# UV_board.net
KiCad netlist of a schematic drawn in Altium Designer
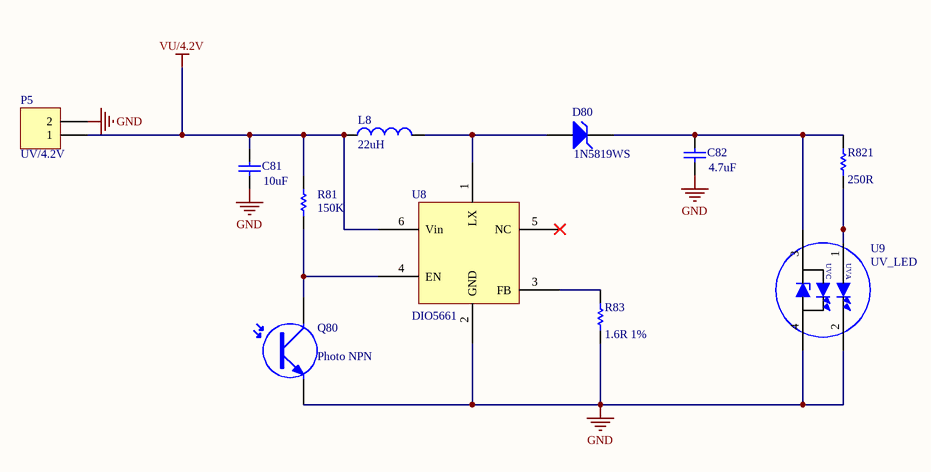
[diagram p0: UV_board.SchDoc]

(export (version "E")
  (design (tool "Eeschema 10.0.6"))
  (components
    (comp (ref "C81")
      (value "10uF")
      (footprint "C0805")
      (description "电容")
      (fields (field (name "Comment") "Cap") (field (name "PUBLISHER") "Altium Limited"))
      (libsource (lib "Miscellaneous Devices") (part "Cap"))
    )
    (comp (ref "C82")
      (value "4.7uF")
      (footprint "C0402")
      (description "电容")
      (fields (field (name "Comment") "Cap") (field (name "PUBLISHER") "Altium Limited"))
      (libsource (lib "Miscellaneous Devices") (part "Cap"))
    )
    (comp (ref "D80")
      (value "1N5819WS")
      (footprint "SOD-323")
      (description "二极管")
      (fields (field (name "PUBLISHER") "Altium Limited"))
      (libsource (lib "Miscellaneous Devices") (part "D Zener"))
    )
    (comp (ref "L8")
      (value "22uH")
      (footprint "CD32")
      (description "功率电感")
      (fields (field (name "Comment") "Inductor") (field (name "PUBLISHER") "Altium Limited"))
      (libsource (lib "Miscellaneous Devices") (part "Inductor"))
    )
    (comp (ref "P5")
      (value "UV/4.2V")
      (footprint "CON_1.25MM_2P")
      (description "UV灯电源接口")
      (fields (field (name "PUBLISHER") "Altium Limited"))
      (libsource (lib "Miscellaneous Connectors") (part "Header 2"))
    )
    (comp (ref "Q80")
      (value "Photo NPN")
      (footprint "PT0603")
      (description "光敏三极管")
      (fields (field (name "PUBLISHER") "Altium Limited"))
      (libsource (lib "Miscellaneous Devices") (part "Photo NPN"))
    )
    (comp (ref "R81")
      (value "150K")
      (footprint "R0402")
      (description "电阻")
      (fields (field (name "Comment") "Res1") (field (name "PUBLISHER") "Altium Limited"))
      (libsource (lib "Miscellaneous Devices") (part "Res1"))
    )
    (comp (ref "R83")
      (value "1.6R 1%")
      (footprint "R0402")
      (description "电阻")
      (fields (field (name "Comment") "Res1") (field (name "PUBLISHER") "Altium Limited"))
      (libsource (lib "Miscellaneous Devices") (part "Res1"))
    )
    (comp (ref "R821")
      (value "250R")
      (footprint "R0402")
      (description "电阻")
      (fields (field (name "Comment") "Res1") (field (name "PUBLISHER") "Altium Limited"))
      (libsource (lib "Miscellaneous Devices") (part "Res1"))
    )
    (comp (ref "U8")
      (value "DIO5661")
      (footprint "SOT23-6-1")
      (description "恒流IC")
      (libsource (lib "shajunbei") (part "DIO5661"))
    )
    (comp (ref "U9") (value "UV_LED") (footprint "SH35AH") (libsource (lib "shajunbei") (part "UV_LED")))
  )
  (nets
    (net (code "1") (name "GND") (class "Default")
      (node (ref "C81") (pin "2") (pinfunction "2_2") (pintype "passive"))
      (node (ref "C82") (pin "2") (pinfunction "2_2") (pintype "passive"))
      (node (ref "P5") (pin "2") (pinfunction "2_2") (pintype "passive"))
      (node (ref "Q80") (pin "3") (pinfunction "E_3") (pintype "passive"))
      (node (ref "R83") (pin "1") (pinfunction "1_1") (pintype "passive"))
      (node (ref "U8") (pin "2") (pinfunction "GND_2") (pintype "passive"))
      (node (ref "U9") (pin "2") (pinfunction "+_2") (pintype "passive"))
      (node (ref "U9") (pin "4") (pinfunction "+_4") (pintype "passive"))
    )
    (net (code "2") (name "Net-(D80-A)") (class "Default")
      (node (ref "D80") (pin "1") (pinfunction "A_1") (pintype "passive"))
      (node (ref "L8") (pin "2") (pinfunction "2_2") (pintype "passive"))
      (node (ref "U8") (pin "1") (pinfunction "LX_1") (pintype "passive"))
    )
    (net (code "3") (name "Net-(D80-K)") (class "Default")
      (node (ref "C82") (pin "1") (pinfunction "1_1") (pintype "passive"))
      (node (ref "D80") (pin "2") (pinfunction "K_2") (pintype "passive"))
      (node (ref "R821") (pin "2") (pinfunction "2_2") (pintype "passive"))
      (node (ref "U9") (pin "3") (pinfunction "+_3") (pintype "passive"))
    )
    (net (code "4") (name "Net-(Q80-C)") (class "Default")
      (node (ref "Q80") (pin "1") (pinfunction "C_1") (pintype "passive"))
      (node (ref "R81") (pin "1") (pinfunction "1_1") (pintype "passive"))
      (node (ref "U8") (pin "4") (pinfunction "EN_4") (pintype "passive"))
    )
    (net (code "5") (name "Net-(R821-Pad1)") (class "Default")
      (node (ref "R821") (pin "1") (pinfunction "1_1") (pintype "passive"))
      (node (ref "U9") (pin "1") (pinfunction "+_1") (pintype "passive"))
    )
    (net (code "6") (name "Net-(U8-FB)") (class "Default")
      (node (ref "R83") (pin "2") (pinfunction "2_2") (pintype "passive"))
      (node (ref "U8") (pin "3") (pinfunction "FB_3") (pintype "passive"))
    )
    (net (code "7") (name "VU{slash}4.2V") (class "Default")
      (node (ref "C81") (pin "1") (pinfunction "1_1") (pintype "passive"))
      (node (ref "L8") (pin "1") (pinfunction "1_1") (pintype "passive"))
      (node (ref "P5") (pin "1") (pinfunction "1_1") (pintype "passive"))
      (node (ref "R81") (pin "2") (pinfunction "2_2") (pintype "passive"))
      (node (ref "U8") (pin "6") (pinfunction "Vin_6") (pintype "passive"))
    )
    (net (code "8") (name "unconnected-(U8-NC-Pad5)") (class "Default")
      (node (ref "U8") (pin "5") (pinfunction "NC_5") (pintype "passive+no_connect"))
    )
  )
)
